# ao.net
KiCad netlist of a schematic drawn in Altium Designer
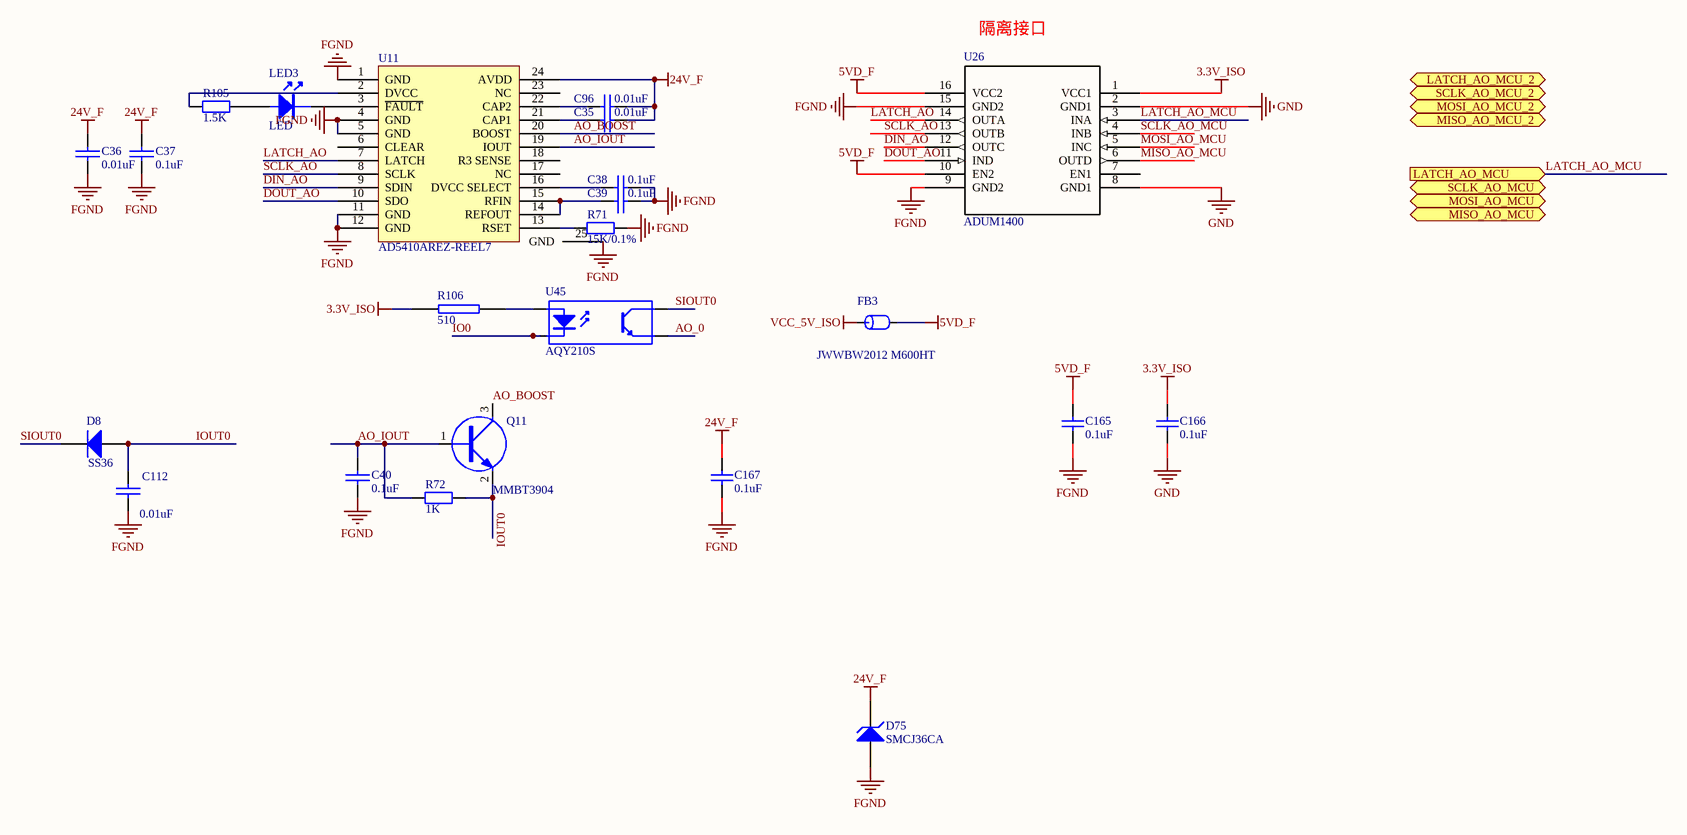
[diagram p0: ao.SchDoc]

(export (version "E")
  (design (tool "Eeschema 10.0.6"))
  (components
    (comp (ref "C35")
      (value "0.01uF")
      (footprint "0603C")
      (description "Capacitor")
      (libsource (lib "*") (part "CAP"))
    )
    (comp (ref "C36")
      (value "0.01uF")
      (footprint "0603C")
      (description "Capacitor")
      (libsource (lib "*") (part "CAP"))
    )
    (comp (ref "C37")
      (value "0.1uF")
      (footprint "0603C")
      (description "Capacitor")
      (libsource (lib "*") (part "CAP"))
    )
    (comp (ref "C38")
      (value "0.1uF")
      (footprint "0603C")
      (description "Capacitor")
      (libsource (lib "*") (part "CAP"))
    )
    (comp (ref "C39")
      (value "0.1uF")
      (footprint "0603C")
      (description "Capacitor")
      (libsource (lib "*") (part "CAP"))
    )
    (comp (ref "C40")
      (value "0.1uF")
      (footprint "0603C")
      (description "Capacitor")
      (libsource (lib "*") (part "CAP"))
    )
    (comp (ref "C96")
      (value "0.01uF")
      (footprint "0603C")
      (description "Capacitor")
      (libsource (lib "*") (part "CAP"))
    )
    (comp (ref "C112")
      (value "0.01uF")
      (footprint "0603C")
      (description "Capacitor")
      (libsource (lib "*") (part "CAP"))
    )
    (comp (ref "C165")
      (value "0.1uF")
      (footprint "0603C")
      (description "Capacitor")
      (fields (field (name "PUBLISHER") "Altium Limited"))
      (libsource (lib "Miscellaneous Devices") (part "Cap"))
    )
    (comp (ref "C166")
      (value "0.1uF")
      (footprint "0603C")
      (description "Capacitor")
      (fields (field (name "PUBLISHER") "Altium Limited"))
      (libsource (lib "Miscellaneous Devices") (part "Cap"))
    )
    (comp (ref "C167")
      (value "0.1uF")
      (footprint "0603C")
      (description "Capacitor")
      (fields (field (name "PUBLISHER") "Altium Limited"))
      (libsource (lib "Miscellaneous Devices") (part "Cap"))
    )
    (comp (ref "D8")
      (value "SS36")
      (footprint "sma")
      (description "1 Amp General Purpose Rectifier")
      (fields (field (name "PUBLISHER") "Altium Limited"))
      (libsource (lib "Miscellaneous Devices") (part "1N4001"))
    )
    (comp (ref "D75")
      (value "SMCJ36CA")
      (footprint "SMC")
      (description "SMBJ36CA")
      (fields (field (name "PUBLISHER") "Altium Limited"))
      (libsource (lib "Miscellaneous Devices") (part "D Zener"))
    )
    (comp (ref "FB3")
      (value "JWWBW2012 M600HT")
      (footprint "0805R")
      (libsource (lib "Schlib_20110825") (part "FB"))
    )
    (comp (ref "LED3") (value "LED") (footprint "0603LED") (libsource (lib "*") (part "LED")))
    (comp (ref "Q11")
      (value "MMBT3904")
      (footprint "SOT23-3")
      (libsource (lib "CenLib") (part "NPN_MMBT3904"))
    )
    (comp (ref "R71") (value "15K/0.1%") (footprint "0603R") (libsource (lib "MQlibrary") (part "Res0805M")))
    (comp (ref "R72") (value "1K") (footprint "0603R") (libsource (lib "MQlibrary") (part "Res0805M")))
    (comp (ref "R105") (value "1.5K") (footprint "0603R") (libsource (lib "MQlibrary") (part "Res0805M")))
    (comp (ref "R106") (value "510") (footprint "0603R") (libsource (lib "*") (part "RES2")))
    (comp (ref "U11")
      (value "AD5410AREZ-REEL7")
      (footprint "AD5410AREZ-REEL7")
      (libsource (lib "Schlib1") (part "AD5410AREZ-REEL7"))
    )
    (comp (ref "U26") (value "ADUM1400") (footprint "SOIC16") (libsource (lib "DI16") (part "ISO7241C")))
    (comp (ref "U45")
      (value "AQY210S")
      (footprint "sop4")
      (description "4-Pin Phototransistor Optocoupler")
      (fields (field (name "PUBLISHER") "Altium Limited"))
      (libsource (lib "Miscellaneous Devices") (part "Optoisolator1"))
    )
  )
  (nets
    (net (code "2") (name "/AO_0") (class "Default")
      (node (ref "U45") (pin "3") (pinfunction "E_3") (pintype "passive"))
    )
    (net (code "3") (name "/AO_BOOST") (class "Default")
      (node (ref "Q11") (pin "3") (pinfunction "C_3") (pintype "passive"))
      (node (ref "U11") (pin "20") (pinfunction "BOOST_20") (pintype "passive"))
    )
    (net (code "4") (name "/AO_IOUT") (class "Default")
      (node (ref "C40") (pin "2") (pinfunction "2_2") (pintype "passive"))
      (node (ref "Q11") (pin "1") (pinfunction "B_1") (pintype "passive"))
      (node (ref "R72") (pin "1") (pinfunction "1_1") (pintype "passive"))
      (node (ref "U11") (pin "19") (pinfunction "IOUT_19") (pintype "passive"))
    )
    (net (code "5") (name "/DIN_AO") (class "Default")
      (node (ref "U11") (pin "9") (pinfunction "SDIN_9") (pintype "passive"))
      (node (ref "U26") (pin "12") (pinfunction "OUTC_12") (pintype "output"))
    )
    (net (code "6") (name "/DOUT_AO") (class "Default")
      (node (ref "U11") (pin "10") (pinfunction "SDO_10") (pintype "passive"))
      (node (ref "U26") (pin "11") (pinfunction "IND_11") (pintype "input"))
    )
    (net (code "7") (name "/IO0") (class "Default")
      (node (ref "U45") (pin "2") (pinfunction "K_2") (pintype "passive"))
    )
    (net (code "8") (name "/IOUT0") (class "Default")
      (node (ref "C112") (pin "2") (pinfunction "2_2") (pintype "passive"))
      (node (ref "D8") (pin "1") (pinfunction "A_1") (pintype "passive"))
      (node (ref "Q11") (pin "2") (pinfunction "E_2") (pintype "passive"))
      (node (ref "R72") (pin "2") (pinfunction "2_2") (pintype "passive"))
    )
    (net (code "9") (name "/LATCH_AO") (class "Default")
      (node (ref "U11") (pin "7") (pinfunction "LATCH_7") (pintype "passive"))
      (node (ref "U26") (pin "14") (pinfunction "OUTA_14") (pintype "output"))
    )
    (net (code "10") (name "/LATCH_AO_MCU") (class "Default")
      (node (ref "U26") (pin "3") (pinfunction "INA_3") (pintype "input"))
    )
    (net (code "12") (name "/MISO_AO_MCU") (class "Default")
      (node (ref "U26") (pin "6") (pinfunction "OUTD_6") (pintype "output"))
    )
    (net (code "14") (name "/MOSI_AO_MCU") (class "Default")
      (node (ref "U26") (pin "5") (pinfunction "INC_5") (pintype "input"))
    )
    (net (code "16") (name "/SCLK_AO") (class "Default")
      (node (ref "U11") (pin "8") (pinfunction "SCLK_8") (pintype "passive"))
      (node (ref "U26") (pin "13") (pinfunction "OUTB_13") (pintype "output"))
    )
    (net (code "17") (name "/SCLK_AO_MCU") (class "Default")
      (node (ref "U26") (pin "4") (pinfunction "INB_4") (pintype "input"))
    )
    (net (code "19") (name "/SIOUT0") (class "Default")
      (node (ref "D8") (pin "2") (pinfunction "K_2") (pintype "passive"))
      (node (ref "U45") (pin "4") (pinfunction "C_4") (pintype "passive"))
    )
    (net (code "20") (name "3.3V_ISO") (class "Default")
      (node (ref "C166") (pin "2") (pinfunction "2_2") (pintype "passive"))
      (node (ref "R106") (pin "2") (pinfunction "2_2") (pintype "passive"))
      (node (ref "U26") (pin "1") (pinfunction "VCC1_1") (pintype "power_in"))
    )
    (net (code "21") (name "5VD_F") (class "Default")
      (node (ref "C165") (pin "2") (pinfunction "2_2") (pintype "passive"))
      (node (ref "FB3") (pin "2") (pintype "passive"))
      (node (ref "U26") (pin "10") (pinfunction "EN2_10") (pintype "passive"))
      (node (ref "U26") (pin "16") (pinfunction "VCC2_16") (pintype "power_in"))
    )
    (net (code "22") (name "24V_F") (class "Default")
      (node (ref "C167") (pin "2") (pinfunction "2_2") (pintype "passive"))
      (node (ref "C35") (pin "2") (pinfunction "2_2") (pintype "passive"))
      (node (ref "C36") (pin "2") (pinfunction "2_2") (pintype "passive"))
      (node (ref "C37") (pin "2") (pinfunction "2_2") (pintype "passive"))
      (node (ref "C96") (pin "2") (pinfunction "2_2") (pintype "passive"))
      (node (ref "D75") (pin "2") (pinfunction "K_2") (pintype "passive"))
      (node (ref "U11") (pin "24") (pinfunction "AVDD_24") (pintype "passive"))
    )
    (net (code "23") (name "FGND") (class "Default")
      (node (ref "C112") (pin "1") (pinfunction "1_1") (pintype "passive"))
      (node (ref "C165") (pin "1") (pinfunction "1_1") (pintype "passive"))
      (node (ref "C167") (pin "1") (pinfunction "1_1") (pintype "passive"))
      (node (ref "C36") (pin "1") (pinfunction "1_1") (pintype "passive"))
      (node (ref "C37") (pin "1") (pinfunction "1_1") (pintype "passive"))
      (node (ref "C38") (pin "2") (pinfunction "2_2") (pintype "passive"))
      (node (ref "C39") (pin "2") (pinfunction "2_2") (pintype "passive"))
      (node (ref "C40") (pin "1") (pinfunction "1_1") (pintype "passive"))
      (node (ref "D75") (pin "1") (pinfunction "A_1") (pintype "passive"))
      (node (ref "R71") (pin "2") (pinfunction "2_2") (pintype "passive"))
      (node (ref "U11") (pin "1") (pinfunction "GND_1") (pintype "passive"))
      (node (ref "U11") (pin "11") (pinfunction "GND_11") (pintype "passive"))
      (node (ref "U11") (pin "12") (pinfunction "GND_12") (pintype "passive"))
      (node (ref "U11") (pin "25") (pinfunction "GND_25") (pintype "passive"))
      (node (ref "U11") (pin "4") (pinfunction "GND_4") (pintype "passive"))
      (node (ref "U11") (pin "5") (pinfunction "GND_5") (pintype "passive"))
      (node (ref "U26") (pin "15") (pinfunction "GND2_15") (pintype "power_in"))
      (node (ref "U26") (pin "9") (pinfunction "GND2_9") (pintype "power_in"))
    )
    (net (code "24") (name "GND") (class "Default")
      (node (ref "C166") (pin "1") (pinfunction "1_1") (pintype "passive"))
      (node (ref "U26") (pin "2") (pinfunction "GND1_2") (pintype "power_in"))
      (node (ref "U26") (pin "8") (pinfunction "GND1_8") (pintype "power_in"))
    )
    (net (code "25") (name "Net-(LED3-Pad1)") (class "Default")
      (node (ref "LED3") (pin "1") (pinfunction "1_1") (pintype "passive"))
      (node (ref "R105") (pin "2") (pinfunction "2_2") (pintype "passive"))
    )
    (net (code "26") (name "Net-(U11-CAP1)") (class "Default")
      (node (ref "C35") (pin "1") (pinfunction "1_1") (pintype "passive"))
      (node (ref "U11") (pin "21") (pinfunction "CAP1_21") (pintype "passive"))
    )
    (net (code "27") (name "Net-(U11-CAP2)") (class "Default")
      (node (ref "C96") (pin "1") (pinfunction "1_1") (pintype "passive"))
      (node (ref "U11") (pin "22") (pinfunction "CAP2_22") (pintype "passive"))
    )
    (net (code "28") (name "Net-(U11-DVCC)") (class "Default")
      (node (ref "R105") (pin "1") (pinfunction "1_1") (pintype "passive"))
      (node (ref "U11") (pin "2") (pinfunction "DVCC_2") (pintype "passive"))
    )
    (net (code "29") (name "Net-(U11-DVCC_SELECT)") (class "Default")
      (node (ref "C38") (pin "1") (pinfunction "1_1") (pintype "passive"))
      (node (ref "U11") (pin "16") (pinfunction "DVCC_SELECT_16") (pintype "passive"))
    )
    (net (code "30") (name "Net-(U11-REFOUT)") (class "Default")
      (node (ref "C39") (pin "1") (pinfunction "1_1") (pintype "passive"))
      (node (ref "U11") (pin "14") (pinfunction "REFOUT_14") (pintype "passive"))
      (node (ref "U11") (pin "15") (pinfunction "RFIN_15") (pintype "passive"))
    )
    (net (code "31") (name "Net-(U11-RSET)") (class "Default")
      (node (ref "R71") (pin "1") (pinfunction "1_1") (pintype "passive"))
      (node (ref "U11") (pin "13") (pinfunction "RSET_13") (pintype "passive"))
    )
    (net (code "32") (name "Net-(U11-~{FAULT})") (class "Default")
      (node (ref "LED3") (pin "2") (pinfunction "2_2") (pintype "passive"))
      (node (ref "U11") (pin "3") (pinfunction "~{FAULT}_3") (pintype "passive"))
    )
    (net (code "33") (name "Net-(U45-A)") (class "Default")
      (node (ref "R106") (pin "1") (pinfunction "1_1") (pintype "passive"))
      (node (ref "U45") (pin "1") (pinfunction "A_1") (pintype "passive"))
    )
    (net (code "34") (name "VCC_5V_ISO") (class "Default") (node (ref "FB3") (pin "1") (pintype "passive")))
    (net (code "35") (name "unconnected-(U11-CLEAR-Pad6)") (class "Default")
      (node (ref "U11") (pin "6") (pinfunction "CLEAR_6") (pintype "passive"))
    )
    (net (code "36") (name "unconnected-(U11-NC-Pad17)") (class "Default")
      (node (ref "U11") (pin "17") (pinfunction "NC_17") (pintype "passive"))
    )
    (net (code "37") (name "unconnected-(U11-NC-Pad23)") (class "Default")
      (node (ref "U11") (pin "23") (pinfunction "NC_23") (pintype "passive"))
    )
    (net (code "38") (name "unconnected-(U11-R3_SENSE-Pad18)") (class "Default")
      (node (ref "U11") (pin "18") (pinfunction "R3_SENSE_18") (pintype "passive"))
    )
    (net (code "39") (name "unconnected-(U26-EN1-Pad7)") (class "Default")
      (node (ref "U26") (pin "7") (pinfunction "EN1_7") (pintype "passive"))
    )
  )
)
